# ARTIC_R2_Module_Breakout.net
KiCad netlist of a schematic drawn in EAGLE
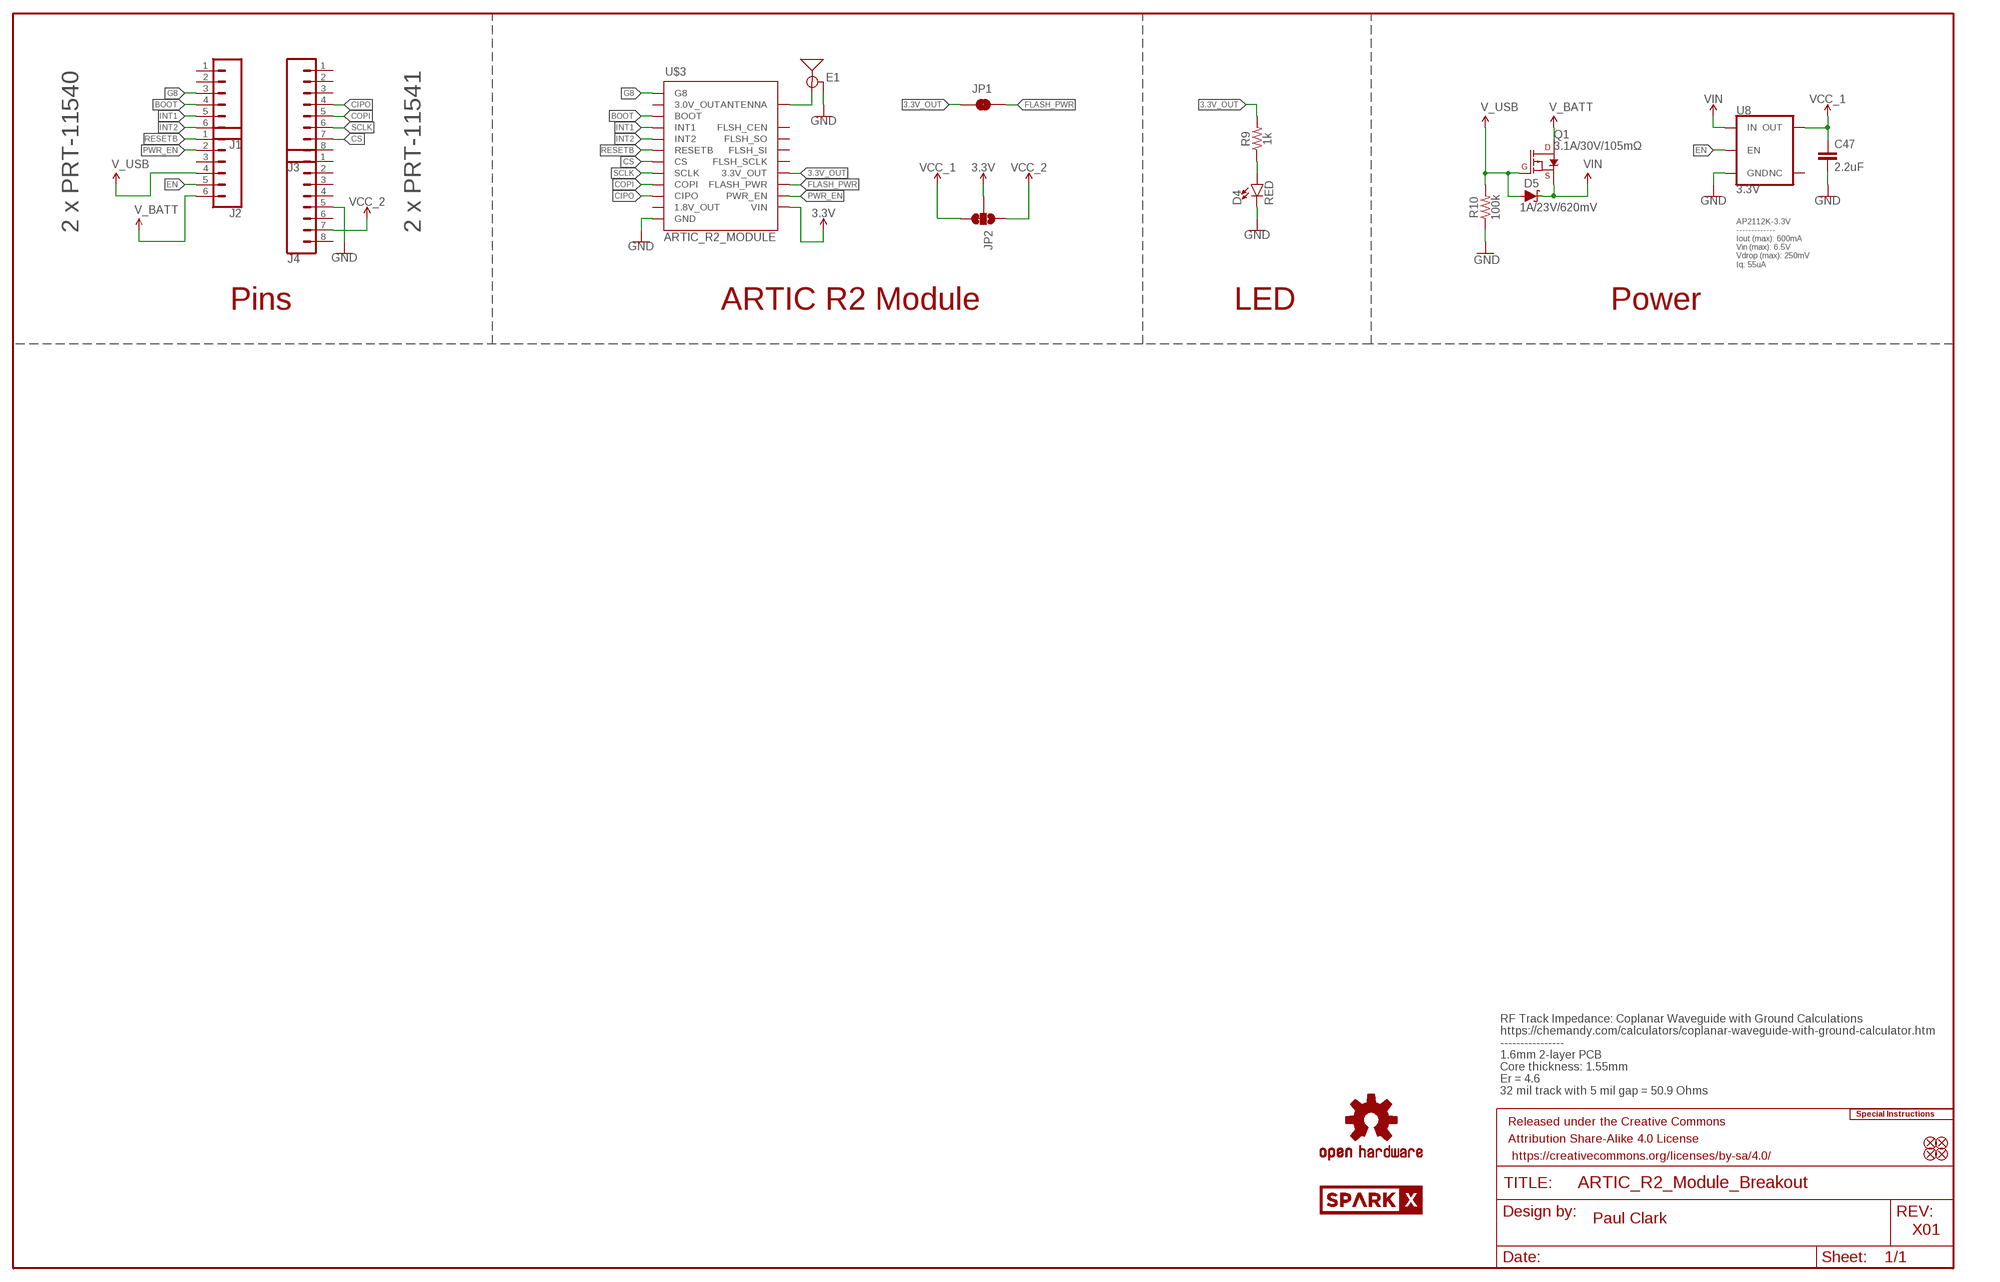
[diagram p0: schematic, sheet 1]

(export (version "E")
  (design (tool "Eeschema 10.0.6"))
  (components
    (comp (ref "C47")
      (value "2.2uF")
      (footprint "eagle-import:0402-TIGHT")
      (libsource (lib "eagle-import") (part "2.2UF-0402_TIGHT-10V-10%-X5R"))
    )
    (comp (ref "D4")
      (value "RED")
      (footprint "eagle-import:LED-0603")
      (libsource (lib "eagle-import") (part "LED-RED0603"))
    )
    (comp (ref "D5")
      (value "1A/23V/620mV")
      (footprint "eagle-import:SOD-323")
      (libsource (lib "eagle-import") (part "DIODE-SCHOTTKY-BAT20J"))
    )
    (comp (ref "E1")
      (value "ANTENNA-SMA-GROUNDEDEDGE_SMA_SMD")
      (footprint "eagle-import:SMA-EDGE-SMD")
      (libsource (lib "eagle-import") (part "ANTENNA-SMA-GROUNDEDEDGE_SMA_SMD"))
    )
    (comp (ref "FD1")
      (value "FIDUCIAL1X2")
      (footprint "eagle-import:FIDUCIAL-1X2")
      (libsource (lib "eagle-import") (part "FIDUCIAL1X2"))
    )
    (comp (ref "FD2")
      (value "FIDUCIAL1X2")
      (footprint "eagle-import:FIDUCIAL-1X2")
      (libsource (lib "eagle-import") (part "FIDUCIAL1X2"))
    )
    (comp (ref "FD3")
      (value "FIDUCIAL1X2")
      (footprint "eagle-import:FIDUCIAL-1X2")
      (libsource (lib "eagle-import") (part "FIDUCIAL1X2"))
    )
    (comp (ref "FD4")
      (value "FIDUCIAL1X2")
      (footprint "eagle-import:FIDUCIAL-1X2")
      (libsource (lib "eagle-import") (part "FIDUCIAL1X2"))
    )
    (comp (ref "FRAME1")
      (value "FRAME-LEDGER")
      (footprint "eagle-import:CREATIVE_COMMONS")
      (libsource (lib "eagle-import") (part "FRAME-LEDGER"))
    )
    (comp (ref "J1")
      (value "CONN_06SMD_MALE")
      (footprint "eagle-import:1X06_SMD_MALE")
      (libsource (lib "eagle-import") (part "CONN_06SMD_MALE"))
    )
    (comp (ref "J2")
      (value "CONN_06SMD_MALE")
      (footprint "eagle-import:1X06_SMD_MALE")
      (libsource (lib "eagle-import") (part "CONN_06SMD_MALE"))
    )
    (comp (ref "J3")
      (value "CONN_08SMD-MALE")
      (footprint "eagle-import:1X08_SMD_MALE")
      (libsource (lib "eagle-import") (part "CONN_08SMD-MALE"))
    )
    (comp (ref "J4")
      (value "CONN_08SMD-MALE")
      (footprint "eagle-import:1X08_SMD_MALE")
      (libsource (lib "eagle-import") (part "CONN_08SMD-MALE"))
    )
    (comp (ref "JP1")
      (value "JUMPER-SMT_2_NC_TRACE_SILK")
      (footprint "eagle-import:SMT-JUMPER_2_NC_TRACE_SILK")
      (libsource (lib "eagle-import") (part "JUMPER-SMT_2_NC_TRACE_SILK"))
    )
    (comp (ref "JP2")
      (value "JUMPER-SMT_3_1-NC_TRACE_SILK")
      (footprint "eagle-import:SMT-JUMPER_3_1-NC_TRACE_SILK")
      (libsource (lib "eagle-import") (part "JUMPER-SMT_3_1-NC_TRACE_SILK"))
    )
    (comp (ref "LOGO1")
      (value "SPECIAL_INSTRUCTIONS-ORDERING")
      (footprint "eagle-import:ORDERING_INSTRUCTIONS")
      (libsource (lib "eagle-import") (part "SPECIAL_INSTRUCTIONS-ORDERING"))
    )
    (comp (ref "LOGO2")
      (value "OSHW-LOGOS")
      (footprint "eagle-import:OSHW-LOGO-S")
      (libsource (lib "eagle-import") (part "OSHW-LOGOS"))
    )
    (comp (ref "LOGO3")
      (value "OSHW-LOGOS")
      (footprint "eagle-import:OSHW-LOGO-S")
      (libsource (lib "eagle-import") (part "OSHW-LOGOS"))
    )
    (comp (ref "Q1")
      (value "3.1A/30V/105mΩ")
      (footprint "eagle-import:SOT23-3")
      (libsource (lib "eagle-import") (part "MOSFET_PCH-DMG2307L"))
    )
    (comp (ref "R9")
      (value "1k")
      (footprint "eagle-import:0402-TIGHT")
      (libsource (lib "eagle-import") (part "1KOHM-0402T-1/16W-1%"))
    )
    (comp (ref "R10")
      (value "100k")
      (footprint "eagle-import:0402-TIGHT")
      (libsource (lib "eagle-import") (part "100KOHM-0402T-1/16W-1%"))
    )
    (comp (ref "SPARKX2")
      (value "SPARKX-LOGO4")
      (footprint "eagle-import:SPARKX-MEDIUM")
      (libsource (lib "eagle-import") (part "SPARKX-LOGO4"))
    )
    (comp (ref "U$3")
      (value "ARTIC_R2_MODULE")
      (footprint "eagle-import:ARTIC_R2_MODULE")
      (libsource (lib "eagle-import") (part "ARTIC_R2_MODULE"))
    )
    (comp (ref "U8")
      (value "3.3V")
      (footprint "eagle-import:SOT23-5")
      (libsource (lib "eagle-import") (part "V_REG_AP2112K-3.3V"))
    )
  )
  (nets
    (net (code "1") (name "3.3V") (class "Default")
      (node (ref "JP2") (pin "2") (pinfunction "2_2") (pintype "passive"))
      (node (ref "U$3") (pin "14") (pinfunction "VIN_14") (pintype "power_in"))
    )
    (net (code "2") (name "3.3V_OUT") (class "Default")
      (node (ref "JP1") (pin "1") (pinfunction "1_1") (pintype "passive"))
      (node (ref "R9") (pin "2") (pinfunction "2_2") (pintype "passive"))
      (node (ref "U$3") (pin "17") (pinfunction "3.3V_OUT_17") (pintype "output"))
    )
    (net (code "3") (name "BOOT") (class "Default")
      (node (ref "J1") (pin "4") (pinfunction "4_4") (pintype "passive"))
      (node (ref "U$3") (pin "3") (pinfunction "BOOT_3") (pintype "input"))
    )
    (net (code "4") (name "CIPO") (class "Default")
      (node (ref "J3") (pin "4") (pinfunction "4_4") (pintype "passive"))
      (node (ref "U$3") (pin "10") (pinfunction "CIPO_10") (pintype "output"))
    )
    (net (code "5") (name "COPI") (class "Default")
      (node (ref "J3") (pin "5") (pinfunction "5_5") (pintype "passive"))
      (node (ref "U$3") (pin "9") (pinfunction "COPI_9") (pintype "input"))
    )
    (net (code "6") (name "CS") (class "Default")
      (node (ref "J3") (pin "7") (pinfunction "7_7") (pintype "passive"))
      (node (ref "U$3") (pin "7") (pinfunction "CS_7") (pintype "input"))
    )
    (net (code "7") (name "EN") (class "Default")
      (node (ref "J2") (pin "5") (pinfunction "5_5") (pintype "passive"))
      (node (ref "U8") (pin "3") (pinfunction "EN_3") (pintype "input"))
    )
    (net (code "8") (name "FLASH_PWR") (class "Default")
      (node (ref "JP1") (pin "2") (pinfunction "2_2") (pintype "passive"))
      (node (ref "U$3") (pin "16") (pinfunction "FLASH_PWR_16") (pintype "input"))
    )
    (net (code "9") (name "G8") (class "Default")
      (node (ref "J1") (pin "3") (pinfunction "3_3") (pintype "passive"))
      (node (ref "U$3") (pin "1") (pinfunction "G8_1") (pintype "input"))
    )
    (net (code "10") (name "GND") (class "Default")
      (node (ref "C47") (pin "2") (pinfunction "2_2") (pintype "passive"))
      (node (ref "D4") (pin "C") (pinfunction "C_C") (pintype "passive"))
      (node (ref "E1") (pin "GND@0") (pinfunction "GND_GND@0") (pintype "bidirectional"))
      (node (ref "E1") (pin "GND@1") (pinfunction "GND_GND@1") (pintype "bidirectional"))
      (node (ref "J4") (pin "5") (pinfunction "5_5") (pintype "passive"))
      (node (ref "R10") (pin "1") (pinfunction "1_1") (pintype "passive"))
      (node (ref "U$3") (pin "12") (pinfunction "GND_12") (pintype "power_in"))
      (node (ref "U$3") (pin "13") (pinfunction "GND_13") (pintype "power_in"))
      (node (ref "U$3") (pin "22") (pinfunction "GND_22") (pintype "power_in"))
      (node (ref "U$3") (pin "24") (pinfunction "GND_24") (pintype "power_in"))
      (node (ref "U8") (pin "2") (pinfunction "GND_2") (pintype "input"))
    )
    (net (code "11") (name "INT1") (class "Default")
      (node (ref "J1") (pin "5") (pinfunction "5_5") (pintype "passive"))
      (node (ref "U$3") (pin "4") (pinfunction "INT1_4") (pintype "output"))
    )
    (net (code "12") (name "INT2") (class "Default")
      (node (ref "J1") (pin "6") (pinfunction "6_6") (pintype "passive"))
      (node (ref "U$3") (pin "5") (pinfunction "INT2_5") (pintype "output"))
    )
    (net (code "13") (name "Net-(D4-PadA)") (class "Default")
      (node (ref "D4") (pin "A") (pinfunction "A_A") (pintype "passive"))
      (node (ref "R9") (pin "1") (pinfunction "1_1") (pintype "passive"))
    )
    (net (code "14") (name "Net-(E1-SIGNAL)") (class "Default")
      (node (ref "E1") (pin "SIG") (pinfunction "SIGNAL_SIG") (pintype "bidirectional"))
      (node (ref "U$3") (pin "23") (pinfunction "ANTENNA_23") (pintype "bidirectional"))
    )
    (net (code "15") (name "PWR_EN") (class "Default")
      (node (ref "J2") (pin "2") (pinfunction "2_2") (pintype "passive"))
      (node (ref "U$3") (pin "15") (pinfunction "PWR_EN_15") (pintype "input"))
    )
    (net (code "16") (name "RESETB") (class "Default")
      (node (ref "J2") (pin "1") (pinfunction "1_1") (pintype "passive"))
      (node (ref "U$3") (pin "6") (pinfunction "RESETB_6") (pintype "input"))
    )
    (net (code "17") (name "SCLK") (class "Default")
      (node (ref "J3") (pin "6") (pinfunction "6_6") (pintype "passive"))
      (node (ref "U$3") (pin "8") (pinfunction "SCLK_8") (pintype "input"))
    )
    (net (code "18") (name "VCC_1") (class "Default")
      (node (ref "C47") (pin "1") (pinfunction "1_1") (pintype "passive"))
      (node (ref "JP2") (pin "3") (pinfunction "3_3") (pintype "passive"))
      (node (ref "U8") (pin "5") (pinfunction "OUT_5") (pintype "passive"))
    )
    (net (code "19") (name "VCC_2") (class "Default")
      (node (ref "J4") (pin "7") (pinfunction "7_7") (pintype "passive"))
      (node (ref "JP2") (pin "1") (pinfunction "1_1") (pintype "passive"))
    )
    (net (code "20") (name "VIN") (class "Default")
      (node (ref "D5") (pin "C") (pinfunction "C_C") (pintype "passive"))
      (node (ref "Q1") (pin "2") (pinfunction "S_2") (pintype "bidirectional"))
      (node (ref "U8") (pin "1") (pinfunction "IN_1") (pintype "input"))
    )
    (net (code "21") (name "V_BATT") (class "Default")
      (node (ref "J2") (pin "6") (pinfunction "6_6") (pintype "passive"))
      (node (ref "Q1") (pin "3") (pinfunction "D_3") (pintype "bidirectional"))
    )
    (net (code "22") (name "V_USB") (class "Default")
      (node (ref "D5") (pin "A") (pinfunction "A_A") (pintype "passive"))
      (node (ref "J2") (pin "4") (pinfunction "4_4") (pintype "passive"))
      (node (ref "Q1") (pin "1") (pinfunction "G_1") (pintype "bidirectional"))
      (node (ref "R10") (pin "2") (pinfunction "2_2") (pintype "passive"))
    )
    (net (code "23") (name "unconnected-(J1-Pad1)") (class "Default")
      (node (ref "J1") (pin "1") (pinfunction "1_1") (pintype "passive"))
    )
    (net (code "24") (name "unconnected-(J1-Pad2)") (class "Default")
      (node (ref "J1") (pin "2") (pinfunction "2_2") (pintype "passive"))
    )
    (net (code "25") (name "unconnected-(J2-Pad3)") (class "Default")
      (node (ref "J2") (pin "3") (pinfunction "3_3") (pintype "passive"))
    )
    (net (code "26") (name "unconnected-(J3-Pad1)") (class "Default")
      (node (ref "J3") (pin "1") (pinfunction "1_1") (pintype "passive"))
    )
    (net (code "27") (name "unconnected-(J3-Pad2)") (class "Default")
      (node (ref "J3") (pin "2") (pinfunction "2_2") (pintype "passive"))
    )
    (net (code "28") (name "unconnected-(J3-Pad3)") (class "Default")
      (node (ref "J3") (pin "3") (pinfunction "3_3") (pintype "passive"))
    )
    (net (code "29") (name "unconnected-(J3-Pad8)") (class "Default")
      (node (ref "J3") (pin "8") (pinfunction "8_8") (pintype "passive"))
    )
    (net (code "30") (name "unconnected-(J4-Pad1)") (class "Default")
      (node (ref "J4") (pin "1") (pinfunction "1_1") (pintype "passive"))
    )
    (net (code "31") (name "unconnected-(J4-Pad2)") (class "Default")
      (node (ref "J4") (pin "2") (pinfunction "2_2") (pintype "passive"))
    )
    (net (code "32") (name "unconnected-(J4-Pad3)") (class "Default")
      (node (ref "J4") (pin "3") (pinfunction "3_3") (pintype "passive"))
    )
    (net (code "33") (name "unconnected-(J4-Pad4)") (class "Default")
      (node (ref "J4") (pin "4") (pinfunction "4_4") (pintype "passive"))
    )
    (net (code "34") (name "unconnected-(J4-Pad6)") (class "Default")
      (node (ref "J4") (pin "6") (pinfunction "6_6") (pintype "passive"))
    )
    (net (code "35") (name "unconnected-(J4-Pad8)") (class "Default")
      (node (ref "J4") (pin "8") (pinfunction "8_8") (pintype "passive"))
    )
    (net (code "36") (name "unconnected-(U$3-1.8V_OUT-Pad11)") (class "Default")
      (node (ref "U$3") (pin "11") (pinfunction "1.8V_OUT_11") (pintype "output"))
    )
    (net (code "37") (name "unconnected-(U$3-3.0V_OUT-Pad2)") (class "Default")
      (node (ref "U$3") (pin "2") (pinfunction "3.0V_OUT_2") (pintype "output"))
    )
    (net (code "38") (name "unconnected-(U$3-FLSH_CEN-Pad21)") (class "Default")
      (node (ref "U$3") (pin "21") (pinfunction "FLSH_CEN_21") (pintype "output"))
    )
    (net (code "39") (name "unconnected-(U$3-FLSH_SCLK-Pad18)") (class "Default")
      (node (ref "U$3") (pin "18") (pinfunction "FLSH_SCLK_18") (pintype "output"))
    )
    (net (code "40") (name "unconnected-(U$3-FLSH_SI-Pad19)") (class "Default")
      (node (ref "U$3") (pin "19") (pinfunction "FLSH_SI_19") (pintype "output"))
    )
    (net (code "41") (name "unconnected-(U$3-FLSH_SO-Pad20)") (class "Default")
      (node (ref "U$3") (pin "20") (pinfunction "FLSH_SO_20") (pintype "input"))
    )
    (net (code "42") (name "unconnected-(U8-NC-Pad4)") (class "Default")
      (node (ref "U8") (pin "4") (pinfunction "NC_4") (pintype "no_connect"))
    )
  )
)
